# B12356-04.net
KiCad netlist of a schematic drawn in EAGLE
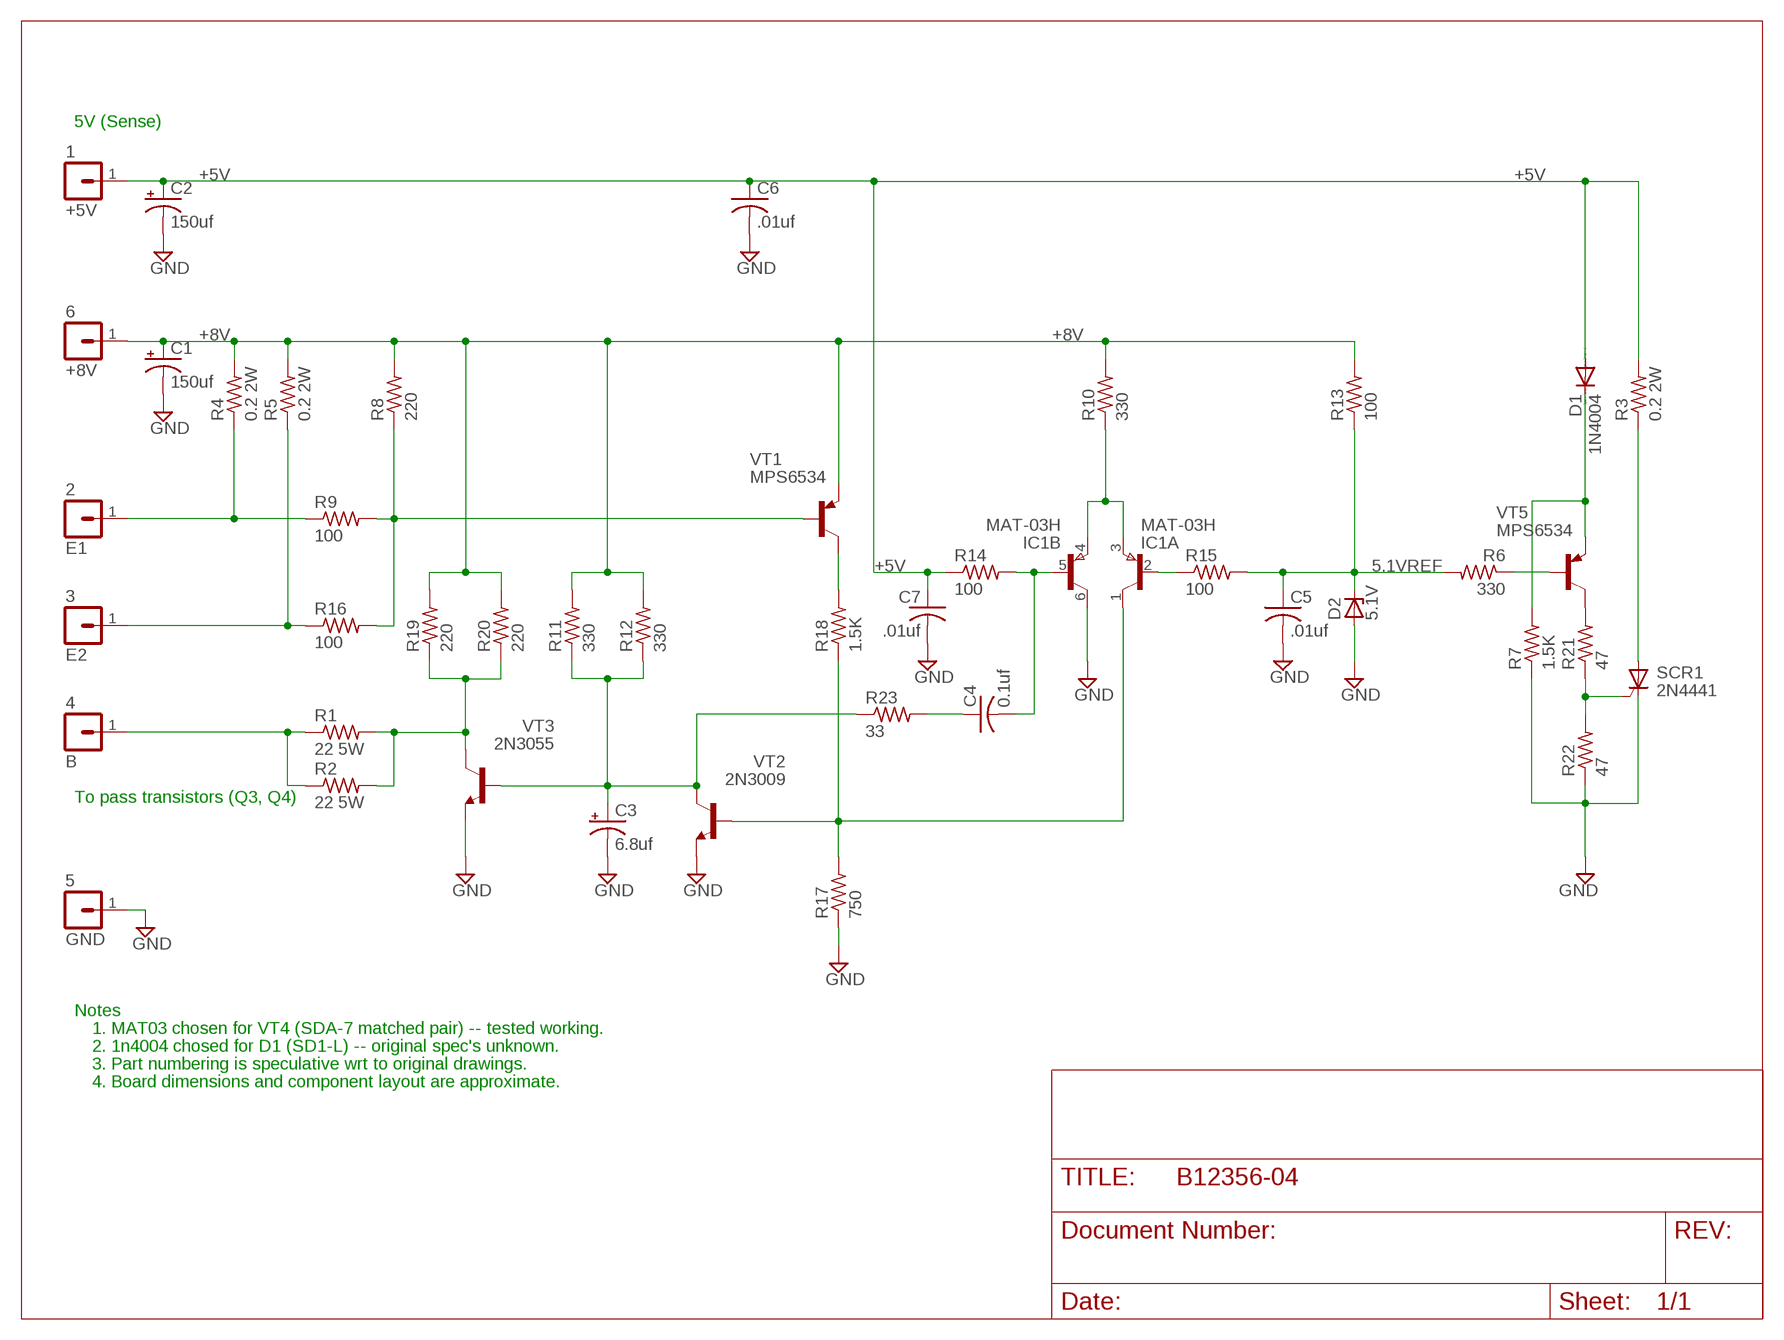
[diagram p0: schematic, sheet 1]

(export (version "E")
  (design (tool "Eeschema 10.0.6"))
  (components
    (comp (ref "+5V")
      (value "1")
      (footprint "eagle-import:SPADELUG")
      (libsource (lib "eagle-import") (part "LUG"))
    )
    (comp (ref "+8V")
      (value "6")
      (footprint "eagle-import:SPADELUG")
      (libsource (lib "eagle-import") (part "LUG"))
    )
    (comp (ref "B")
      (value "4")
      (footprint "eagle-import:SPADELUG")
      (libsource (lib "eagle-import") (part "LUG"))
    )
    (comp (ref "C1")
      (value "150uf")
      (footprint "eagle-import:E22-6")
      (libsource (lib "eagle-import") (part "CPOL-USE22-6AXIAL"))
    )
    (comp (ref "C2")
      (value "150uf")
      (footprint "eagle-import:E22-6")
      (libsource (lib "eagle-import") (part "CPOL-USE22-6AXIAL"))
    )
    (comp (ref "C3")
      (value "6.8uf")
      (footprint "eagle-import:E15-5")
      (libsource (lib "eagle-import") (part "CPOL-USE15-5AXIAL"))
    )
    (comp (ref "C4")
      (value "0.1uf")
      (footprint "eagle-import:C102-064X133")
      (libsource (lib "eagle-import") (part "C-US102-064X133"))
    )
    (comp (ref "C5")
      (value ".01uf")
      (footprint "eagle-import:C050-025X075")
      (libsource (lib "eagle-import") (part "C-US050-025X075"))
    )
    (comp (ref "C6")
      (value ".01uf")
      (footprint "eagle-import:C050-025X075")
      (libsource (lib "eagle-import") (part "C-US050-025X075"))
    )
    (comp (ref "C7")
      (value ".01uf")
      (footprint "eagle-import:C050-025X075")
      (libsource (lib "eagle-import") (part "C-US050-025X075"))
    )
    (comp (ref "D1")
      (value "1N4004")
      (footprint "eagle-import:DO41-10")
      (libsource (lib "eagle-import") (part "1N4004"))
    )
    (comp (ref "D2")
      (value "5.1V")
      (footprint "eagle-import:DO41Z10")
      (libsource (lib "eagle-import") (part "ZENER-DIODEDO41Z10"))
    )
    (comp (ref "E1")
      (value "2")
      (footprint "eagle-import:SPADELUG")
      (libsource (lib "eagle-import") (part "LUG"))
    )
    (comp (ref "E2")
      (value "3")
      (footprint "eagle-import:SPADELUG")
      (libsource (lib "eagle-import") (part "LUG"))
    )
    (comp (ref "GND")
      (value "5")
      (footprint "eagle-import:SPADELUG")
      (libsource (lib "eagle-import") (part "LUG"))
    )
    (comp (ref "IC1")
      (value "MAT-03H")
      (footprint "eagle-import:TO78")
      (libsource (lib "eagle-import") (part "MAT-03H"))
    )
    (comp (ref "R1")
      (value "22 5W")
      (footprint "eagle-import:P0817_22")
      (libsource (lib "eagle-import") (part "R-US_0817/22"))
    )
    (comp (ref "R2")
      (value "22 5W")
      (footprint "eagle-import:P0817_22")
      (libsource (lib "eagle-import") (part "R-US_0817/22"))
    )
    (comp (ref "R3")
      (value "0.2 2W")
      (footprint "eagle-import:0414_15")
      (libsource (lib "eagle-import") (part "R-US_0414/15"))
    )
    (comp (ref "R4")
      (value "0.2 2W")
      (footprint "eagle-import:0414_15")
      (libsource (lib "eagle-import") (part "R-US_0414/15"))
    )
    (comp (ref "R5")
      (value "0.2 2W")
      (footprint "eagle-import:0414_15")
      (libsource (lib "eagle-import") (part "R-US_0414/15"))
    )
    (comp (ref "R6")
      (value "330")
      (footprint "eagle-import:0207_10")
      (libsource (lib "eagle-import") (part "R-US_0207/10"))
    )
    (comp (ref "R7")
      (value "1.5K")
      (footprint "eagle-import:0207_10")
      (libsource (lib "eagle-import") (part "R-US_0207/10"))
    )
    (comp (ref "R8")
      (value "220")
      (footprint "eagle-import:0207_10")
      (libsource (lib "eagle-import") (part "R-US_0207/10"))
    )
    (comp (ref "R9")
      (value "100")
      (footprint "eagle-import:0207_10")
      (libsource (lib "eagle-import") (part "R-US_0207/10"))
    )
    (comp (ref "R10")
      (value "330")
      (footprint "eagle-import:0207_10")
      (libsource (lib "eagle-import") (part "R-US_0207/10"))
    )
    (comp (ref "R11")
      (value "330")
      (footprint "eagle-import:0207_10")
      (libsource (lib "eagle-import") (part "R-US_0207/10"))
    )
    (comp (ref "R12")
      (value "330")
      (footprint "eagle-import:0207_10")
      (libsource (lib "eagle-import") (part "R-US_0207/10"))
    )
    (comp (ref "R13")
      (value "100")
      (footprint "eagle-import:0207_10")
      (libsource (lib "eagle-import") (part "R-US_0207/10"))
    )
    (comp (ref "R14")
      (value "100")
      (footprint "eagle-import:0207_10")
      (libsource (lib "eagle-import") (part "R-US_0207/10"))
    )
    (comp (ref "R15")
      (value "100")
      (footprint "eagle-import:0207_10")
      (libsource (lib "eagle-import") (part "R-US_0207/10"))
    )
    (comp (ref "R16")
      (value "100")
      (footprint "eagle-import:0207_10")
      (libsource (lib "eagle-import") (part "R-US_0207/10"))
    )
    (comp (ref "R17")
      (value "750")
      (footprint "eagle-import:0207_10")
      (libsource (lib "eagle-import") (part "R-US_0207/10"))
    )
    (comp (ref "R18")
      (value "1.5K")
      (footprint "eagle-import:0207_10")
      (libsource (lib "eagle-import") (part "R-US_0207/10"))
    )
    (comp (ref "R19")
      (value "220")
      (footprint "eagle-import:0207_10")
      (libsource (lib "eagle-import") (part "R-US_0207/10"))
    )
    (comp (ref "R20")
      (value "220")
      (footprint "eagle-import:0207_10")
      (libsource (lib "eagle-import") (part "R-US_0207/10"))
    )
    (comp (ref "R21")
      (value "47")
      (footprint "eagle-import:0207_10")
      (libsource (lib "eagle-import") (part "R-US_0207/10"))
    )
    (comp (ref "R22")
      (value "47")
      (footprint "eagle-import:0207_10")
      (libsource (lib "eagle-import") (part "R-US_0207/10"))
    )
    (comp (ref "R23")
      (value "33")
      (footprint "eagle-import:0207_10")
      (libsource (lib "eagle-import") (part "R-US_0207/10"))
    )
    (comp (ref "SCR1")
      (value "2N4441")
      (footprint "eagle-import:TO220CL")
      (libsource (lib "eagle-import") (part "BT151"))
    )
    (comp (ref "VT1")
      (value "MPS6534")
      (footprint "eagle-import:TO92-BCE")
      (libsource (lib "eagle-import") (part "-PNP-TO92-BCEMPSA56"))
    )
    (comp (ref "VT2")
      (value "2N3009")
      (footprint "eagle-import:TO18")
      (libsource (lib "eagle-import") (part "2N2222"))
    )
    (comp (ref "VT3")
      (value "2N3055")
      (footprint "eagle-import:TO3")
      (libsource (lib "eagle-import") (part "2N3055"))
    )
    (comp (ref "VT5")
      (value "MPS6534")
      (footprint "eagle-import:TO92-BCE")
      (libsource (lib "eagle-import") (part "-PNP-TO92-BCEMPSA56"))
    )
  )
  (nets
    (net (code "1") (name "/+5V") (class "Default")
      (node (ref "+5V") (pin "1") (pinfunction "1_1") (pintype "passive"))
      (node (ref "C2") (pin "+") (pinfunction "+_+") (pintype "passive"))
      (node (ref "C6") (pin "1") (pinfunction "1_1") (pintype "passive"))
      (node (ref "C7") (pin "1") (pinfunction "1_1") (pintype "passive"))
      (node (ref "D1") (pin "A") (pinfunction "A_A") (pintype "passive"))
      (node (ref "R14") (pin "1") (pinfunction "1_1") (pintype "passive"))
      (node (ref "R3") (pin "2") (pinfunction "2_2") (pintype "passive"))
    )
    (net (code "2") (name "/+8V") (class "Default")
      (node (ref "+8V") (pin "1") (pinfunction "1_1") (pintype "passive"))
      (node (ref "C1") (pin "+") (pinfunction "+_+") (pintype "passive"))
      (node (ref "R10") (pin "2") (pinfunction "2_2") (pintype "passive"))
      (node (ref "R11") (pin "2") (pinfunction "2_2") (pintype "passive"))
      (node (ref "R12") (pin "2") (pinfunction "2_2") (pintype "passive"))
      (node (ref "R13") (pin "2") (pinfunction "2_2") (pintype "passive"))
      (node (ref "R19") (pin "2") (pinfunction "2_2") (pintype "passive"))
      (node (ref "R20") (pin "2") (pinfunction "2_2") (pintype "passive"))
      (node (ref "R4") (pin "2") (pinfunction "2_2") (pintype "passive"))
      (node (ref "R5") (pin "2") (pinfunction "2_2") (pintype "passive"))
      (node (ref "R8") (pin "2") (pinfunction "2_2") (pintype "passive"))
      (node (ref "VT1") (pin "E") (pinfunction "E_E") (pintype "passive"))
    )
    (net (code "3") (name "/5.1VREF") (class "Default")
      (node (ref "C5") (pin "1") (pinfunction "1_1") (pintype "passive"))
      (node (ref "D2") (pin "C") (pinfunction "C_C") (pintype "passive"))
      (node (ref "R13") (pin "1") (pinfunction "1_1") (pintype "passive"))
      (node (ref "R15") (pin "2") (pinfunction "2_2") (pintype "passive"))
      (node (ref "R6") (pin "2") (pinfunction "2_2") (pintype "passive"))
    )
    (net (code "4") (name "GND") (class "Default")
      (node (ref "C1") (pin "-") (pinfunction "-_-") (pintype "passive"))
      (node (ref "C2") (pin "-") (pinfunction "-_-") (pintype "passive"))
      (node (ref "C3") (pin "-") (pinfunction "-_-") (pintype "passive"))
      (node (ref "C5") (pin "2") (pinfunction "2_2") (pintype "passive"))
      (node (ref "C6") (pin "2") (pinfunction "2_2") (pintype "passive"))
      (node (ref "C7") (pin "2") (pinfunction "2_2") (pintype "passive"))
      (node (ref "D2") (pin "A") (pinfunction "A_A") (pintype "passive"))
      (node (ref "GND") (pin "1") (pinfunction "1_1") (pintype "passive"))
      (node (ref "IC1") (pin "6") (pinfunction "C_6") (pintype "passive"))
      (node (ref "R17") (pin "1") (pinfunction "1_1") (pintype "passive"))
      (node (ref "R22") (pin "1") (pinfunction "1_1") (pintype "passive"))
      (node (ref "R7") (pin "1") (pinfunction "1_1") (pintype "passive"))
      (node (ref "SCR1") (pin "C") (pinfunction "C_C") (pintype "passive"))
      (node (ref "VT2") (pin "1") (pinfunction "E_1") (pintype "passive"))
      (node (ref "VT3") (pin "E") (pinfunction "E_E") (pintype "passive"))
    )
    (net (code "5") (name "Net-(B-Pad1)") (class "Default")
      (node (ref "B") (pin "1") (pinfunction "1_1") (pintype "passive"))
      (node (ref "R1") (pin "1") (pinfunction "1_1") (pintype "passive"))
      (node (ref "R2") (pin "1") (pinfunction "1_1") (pintype "passive"))
    )
    (net (code "6") (name "Net-(C4-Pad1)") (class "Default")
      (node (ref "C4") (pin "1") (pinfunction "1_1") (pintype "passive"))
      (node (ref "R23") (pin "2") (pinfunction "2_2") (pintype "passive"))
    )
    (net (code "7") (name "Net-(D1-PadC)") (class "Default")
      (node (ref "D1") (pin "C") (pinfunction "C_C") (pintype "passive"))
      (node (ref "R7") (pin "2") (pinfunction "2_2") (pintype "passive"))
      (node (ref "VT5") (pin "E") (pinfunction "E_E") (pintype "passive"))
    )
    (net (code "8") (name "Net-(E1-Pad1)") (class "Default")
      (node (ref "E1") (pin "1") (pinfunction "1_1") (pintype "passive"))
      (node (ref "R4") (pin "1") (pinfunction "1_1") (pintype "passive"))
      (node (ref "R9") (pin "1") (pinfunction "1_1") (pintype "passive"))
    )
    (net (code "9") (name "Net-(E2-Pad1)") (class "Default")
      (node (ref "E2") (pin "1") (pinfunction "1_1") (pintype "passive"))
      (node (ref "R16") (pin "1") (pinfunction "1_1") (pintype "passive"))
      (node (ref "R5") (pin "1") (pinfunction "1_1") (pintype "passive"))
    )
    (net (code "10") (name "Net-(IC1A-B)") (class "Default")
      (node (ref "IC1") (pin "2") (pinfunction "B_2") (pintype "passive"))
      (node (ref "R15") (pin "1") (pinfunction "1_1") (pintype "passive"))
    )
    (net (code "11") (name "Net-(IC1A-C)") (class "Default")
      (node (ref "IC1") (pin "1") (pinfunction "C_1") (pintype "passive"))
      (node (ref "R17") (pin "2") (pinfunction "2_2") (pintype "passive"))
      (node (ref "R18") (pin "1") (pinfunction "1_1") (pintype "passive"))
      (node (ref "VT2") (pin "2") (pinfunction "B_2") (pintype "passive"))
    )
    (net (code "12") (name "Net-(IC1A-E)") (class "Default")
      (node (ref "IC1") (pin "3") (pinfunction "E_3") (pintype "passive"))
      (node (ref "IC1") (pin "4") (pinfunction "E_4") (pintype "passive"))
      (node (ref "R10") (pin "1") (pinfunction "1_1") (pintype "passive"))
    )
    (net (code "13") (name "Net-(IC1B-B)") (class "Default")
      (node (ref "C4") (pin "2") (pinfunction "2_2") (pintype "passive"))
      (node (ref "IC1") (pin "5") (pinfunction "B_5") (pintype "passive"))
      (node (ref "R14") (pin "2") (pinfunction "2_2") (pintype "passive"))
    )
    (net (code "14") (name "Net-(R1-Pad2)") (class "Default")
      (node (ref "R1") (pin "2") (pinfunction "2_2") (pintype "passive"))
      (node (ref "R19") (pin "1") (pinfunction "1_1") (pintype "passive"))
      (node (ref "R2") (pin "2") (pinfunction "2_2") (pintype "passive"))
      (node (ref "R20") (pin "1") (pinfunction "1_1") (pintype "passive"))
      (node (ref "VT3") (pin "C") (pinfunction "C_C") (pintype "passive"))
      (node (ref "VT3") (pin "C/") (pinfunction "C_C/") (pintype "passive"))
    )
    (net (code "15") (name "Net-(R3-Pad1)") (class "Default")
      (node (ref "R3") (pin "1") (pinfunction "1_1") (pintype "passive"))
      (node (ref "SCR1") (pin "A") (pinfunction "A_A") (pintype "passive"))
    )
    (net (code "16") (name "Net-(R6-Pad1)") (class "Default")
      (node (ref "R6") (pin "1") (pinfunction "1_1") (pintype "passive"))
      (node (ref "VT5") (pin "B") (pinfunction "B_B") (pintype "passive"))
    )
    (net (code "17") (name "Net-(R16-Pad2)") (class "Default")
      (node (ref "R16") (pin "2") (pinfunction "2_2") (pintype "passive"))
      (node (ref "R8") (pin "1") (pinfunction "1_1") (pintype "passive"))
      (node (ref "R9") (pin "2") (pinfunction "2_2") (pintype "passive"))
      (node (ref "VT1") (pin "B") (pinfunction "B_B") (pintype "passive"))
    )
    (net (code "18") (name "Net-(R18-Pad2)") (class "Default")
      (node (ref "R18") (pin "2") (pinfunction "2_2") (pintype "passive"))
      (node (ref "VT1") (pin "C") (pinfunction "C_C") (pintype "passive"))
    )
    (net (code "19") (name "Net-(R21-Pad1)") (class "Default")
      (node (ref "R21") (pin "1") (pinfunction "1_1") (pintype "passive"))
      (node (ref "R22") (pin "2") (pinfunction "2_2") (pintype "passive"))
      (node (ref "SCR1") (pin "G") (pinfunction "G_G") (pintype "passive"))
    )
    (net (code "20") (name "Net-(R21-Pad2)") (class "Default")
      (node (ref "R21") (pin "2") (pinfunction "2_2") (pintype "passive"))
      (node (ref "VT5") (pin "C") (pinfunction "C_C") (pintype "passive"))
    )
    (net (code "21") (name "Net-(VT2-C)") (class "Default")
      (node (ref "C3") (pin "+") (pinfunction "+_+") (pintype "passive"))
      (node (ref "R11") (pin "1") (pinfunction "1_1") (pintype "passive"))
      (node (ref "R12") (pin "1") (pinfunction "1_1") (pintype "passive"))
      (node (ref "R23") (pin "1") (pinfunction "1_1") (pintype "passive"))
      (node (ref "VT2") (pin "3") (pinfunction "C_3") (pintype "passive"))
      (node (ref "VT3") (pin "B") (pinfunction "B_B") (pintype "passive"))
    )
  )
)
